# inclinometer_adxl335.net
KiCad netlist of a schematic drawn in EAGLE
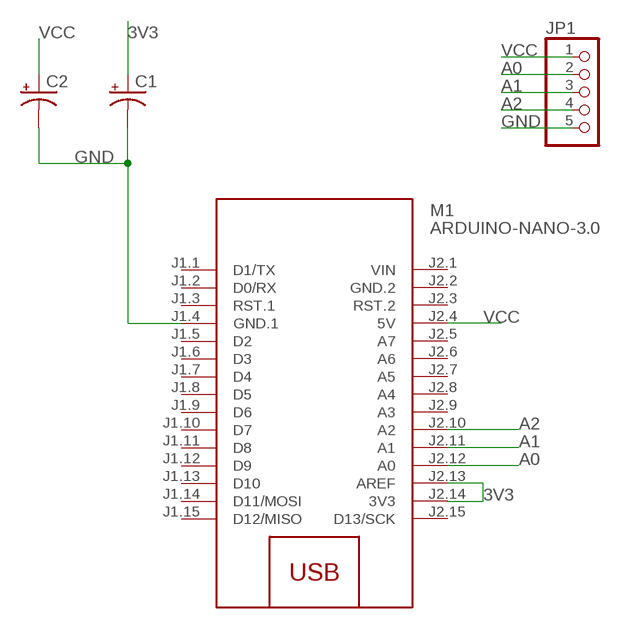
[diagram p0: schematic, sheet 1]

(export (version "E")
  (design (tool "Eeschema 10.0.6"))
  (components
    (comp (ref "C1")
      (value "CPOL-USE2.5-6")
      (footprint "eagle-import:E2,5-6")
      (libsource (lib "eagle-import") (part "CPOL-USE2.5-6"))
    )
    (comp (ref "C2")
      (value "CPOL-USE2.5-6")
      (footprint "eagle-import:E2,5-6")
      (libsource (lib "eagle-import") (part "CPOL-USE2.5-6"))
    )
    (comp (ref "JP1")
      (value "PINHD-1X5")
      (footprint "eagle-import:1X05")
      (libsource (lib "eagle-import") (part "PINHD-1X5"))
    )
    (comp (ref "M1")
      (value "ARDUINO-NANO-3.0")
      (footprint "eagle-import:ARDUINO-NANO-3.0")
      (libsource (lib "eagle-import") (part "ARDUINO-NANO-3.0"))
    )
  )
  (nets
    (net (code "1") (name "/3V3") (class "Default")
      (node (ref "C1") (pin "+") (pinfunction "+_+") (pintype "passive"))
      (node (ref "M1") (pin "J2.13") (pinfunction "AREF_J2.13") (pintype "bidirectional"))
      (node (ref "M1") (pin "J2.14") (pinfunction "3V3_J2.14") (pintype "power_in"))
    )
    (net (code "2") (name "/A0") (class "Default")
      (node (ref "JP1") (pin "2") (pinfunction "2_2") (pintype "passive"))
      (node (ref "M1") (pin "J2.12") (pinfunction "A0_J2.12") (pintype "bidirectional"))
    )
    (net (code "3") (name "/A1") (class "Default")
      (node (ref "JP1") (pin "3") (pinfunction "3_3") (pintype "passive"))
      (node (ref "M1") (pin "J2.11") (pinfunction "A1_J2.11") (pintype "bidirectional"))
    )
    (net (code "4") (name "/A2") (class "Default")
      (node (ref "JP1") (pin "4") (pinfunction "4_4") (pintype "passive"))
      (node (ref "M1") (pin "J2.10") (pinfunction "A2_J2.10") (pintype "bidirectional"))
    )
    (net (code "5") (name "/GND") (class "Default")
      (node (ref "C1") (pin "-") (pinfunction "-_-") (pintype "passive"))
      (node (ref "C2") (pin "-") (pinfunction "-_-") (pintype "passive"))
      (node (ref "JP1") (pin "5") (pinfunction "5_5") (pintype "passive"))
      (node (ref "M1") (pin "J1.4") (pinfunction "GND.1_J1.4") (pintype "power_in"))
    )
    (net (code "6") (name "/GND.2") (class "Default")
      (node (ref "M1") (pin "J2.2") (pinfunction "GND.2_J2.2") (pintype "power_in"))
    )
    (net (code "7") (name "/VCC") (class "Default")
      (node (ref "C2") (pin "+") (pinfunction "+_+") (pintype "passive"))
      (node (ref "JP1") (pin "1") (pinfunction "1_1") (pintype "passive"))
      (node (ref "M1") (pin "J2.4") (pinfunction "5V_J2.4") (pintype "power_in"))
    )
    (net (code "8") (name "/VIN") (class "Default")
      (node (ref "M1") (pin "J2.1") (pinfunction "VIN_J2.1") (pintype "power_in"))
    )
    (net (code "9") (name "unconnected-(M1-A3-PadJ2.9)") (class "Default")
      (node (ref "M1") (pin "J2.9") (pinfunction "A3_J2.9") (pintype "bidirectional"))
    )
    (net (code "10") (name "unconnected-(M1-A4-PadJ2.8)") (class "Default")
      (node (ref "M1") (pin "J2.8") (pinfunction "A4_J2.8") (pintype "bidirectional"))
    )
    (net (code "11") (name "unconnected-(M1-A5-PadJ2.7)") (class "Default")
      (node (ref "M1") (pin "J2.7") (pinfunction "A5_J2.7") (pintype "bidirectional"))
    )
    (net (code "12") (name "unconnected-(M1-A6-PadJ2.6)") (class "Default")
      (node (ref "M1") (pin "J2.6") (pinfunction "A6_J2.6") (pintype "bidirectional"))
    )
    (net (code "13") (name "unconnected-(M1-A7-PadJ2.5)") (class "Default")
      (node (ref "M1") (pin "J2.5") (pinfunction "A7_J2.5") (pintype "bidirectional"))
    )
    (net (code "14") (name "unconnected-(M1-D0{slash}RX-PadJ1.2)") (class "Default")
      (node (ref "M1") (pin "J1.2") (pinfunction "D0/RX_J1.2") (pintype "bidirectional"))
    )
    (net (code "15") (name "unconnected-(M1-D1{slash}TX-PadJ1.1)") (class "Default")
      (node (ref "M1") (pin "J1.1") (pinfunction "D1/TX_J1.1") (pintype "bidirectional"))
    )
    (net (code "16") (name "unconnected-(M1-D2-PadJ1.5)") (class "Default")
      (node (ref "M1") (pin "J1.5") (pinfunction "D2_J1.5") (pintype "bidirectional"))
    )
    (net (code "17") (name "unconnected-(M1-D3-PadJ1.6)") (class "Default")
      (node (ref "M1") (pin "J1.6") (pinfunction "D3_J1.6") (pintype "bidirectional"))
    )
    (net (code "18") (name "unconnected-(M1-D4-PadJ1.7)") (class "Default")
      (node (ref "M1") (pin "J1.7") (pinfunction "D4_J1.7") (pintype "bidirectional"))
    )
    (net (code "19") (name "unconnected-(M1-D5-PadJ1.8)") (class "Default")
      (node (ref "M1") (pin "J1.8") (pinfunction "D5_J1.8") (pintype "bidirectional"))
    )
    (net (code "20") (name "unconnected-(M1-D6-PadJ1.9)") (class "Default")
      (node (ref "M1") (pin "J1.9") (pinfunction "D6_J1.9") (pintype "bidirectional"))
    )
    (net (code "21") (name "unconnected-(M1-D7-PadJ1.10)") (class "Default")
      (node (ref "M1") (pin "J1.10") (pinfunction "D7_J1.10") (pintype "bidirectional"))
    )
    (net (code "22") (name "unconnected-(M1-D8-PadJ1.11)") (class "Default")
      (node (ref "M1") (pin "J1.11") (pinfunction "D8_J1.11") (pintype "bidirectional"))
    )
    (net (code "23") (name "unconnected-(M1-D9-PadJ1.12)") (class "Default")
      (node (ref "M1") (pin "J1.12") (pinfunction "D9_J1.12") (pintype "bidirectional"))
    )
    (net (code "24") (name "unconnected-(M1-D10-PadJ1.13)") (class "Default")
      (node (ref "M1") (pin "J1.13") (pinfunction "D10_J1.13") (pintype "bidirectional"))
    )
    (net (code "25") (name "unconnected-(M1-D11{slash}MOSI-PadJ1.14)") (class "Default")
      (node (ref "M1") (pin "J1.14") (pinfunction "D11/MOSI_J1.14") (pintype "bidirectional"))
    )
    (net (code "26") (name "unconnected-(M1-D12{slash}MISO-PadJ1.15)") (class "Default")
      (node (ref "M1") (pin "J1.15") (pinfunction "D12/MISO_J1.15") (pintype "bidirectional"))
    )
    (net (code "27") (name "unconnected-(M1-D13{slash}SCK-PadJ2.15)") (class "Default")
      (node (ref "M1") (pin "J2.15") (pinfunction "D13/SCK_J2.15") (pintype "bidirectional"))
    )
    (net (code "28") (name "unconnected-(M1-RST.1-PadJ1.3)") (class "Default")
      (node (ref "M1") (pin "J1.3") (pinfunction "RST.1_J1.3") (pintype "bidirectional"))
    )
    (net (code "29") (name "unconnected-(M1-RST.2-PadJ2.3)") (class "Default")
      (node (ref "M1") (pin "J2.3") (pinfunction "RST.2_J2.3") (pintype "bidirectional"))
    )
  )
)
